# ActiveHeadphonePTH.net
KiCad netlist of a schematic drawn in EAGLE
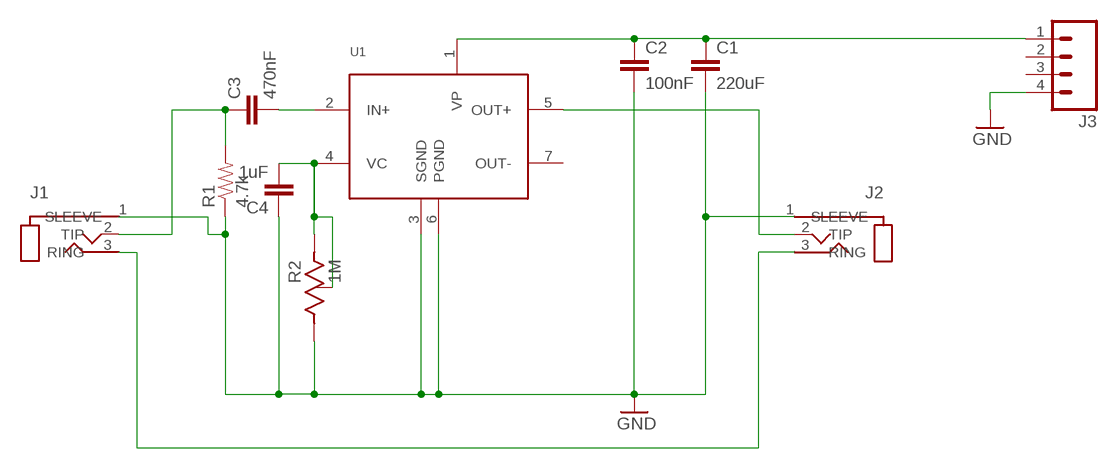
[diagram p0: schematic, sheet 1]

(export (version "E")
  (design (tool "Eeschema 10.0.6"))
  (components
    (comp (ref "C1")
      (value "220uF")
      (footprint "eagle-import:CAP-PTH-5MM")
      (libsource (lib "eagle-import") (part "CAPPTH1"))
    )
    (comp (ref "C2")
      (value "100nF")
      (footprint "eagle-import:CAP-PTH-5MM")
      (libsource (lib "eagle-import") (part "CAPPTH1"))
    )
    (comp (ref "C3")
      (value "470nF")
      (footprint "eagle-import:CAP-PTH-SMALL")
      (libsource (lib "eagle-import") (part "CAPPTH"))
    )
    (comp (ref "C4")
      (value "1uF")
      (footprint "eagle-import:CAP-PTH-SMALL")
      (libsource (lib "eagle-import") (part "CAPPTH"))
    )
    (comp (ref "J1")
      (value "SJ1-35XXPTH")
      (footprint "eagle-import:SJ1-3523N")
      (libsource (lib "eagle-import") (part "SJ1-35XXPTH"))
    )
    (comp (ref "J2")
      (value "SJ1-35XXPTH")
      (footprint "eagle-import:SJ1-3523N")
      (libsource (lib "eagle-import") (part "SJ1-35XXPTH"))
    )
    (comp (ref "J3")
      (value "M04PTH")
      (footprint "eagle-import:1X04")
      (libsource (lib "eagle-import") (part "M04PTH"))
    )
    (comp (ref "R1")
      (value "4.7k")
      (footprint "eagle-import:AXIAL-0.4")
      (libsource (lib "eagle-import") (part "RESISTORPTH-1/4W"))
    )
    (comp (ref "R2")
      (value "1M")
      (footprint "eagle-import:3352T")
      (libsource (lib "eagle-import") (part "3352T"))
    )
    (comp (ref "U1")
      (value "TDA7052")
      (footprint "eagle-import:DIL-8")
      (libsource (lib "eagle-import") (part "TDA7052"))
    )
  )
  (nets
    (net (code "1") (name "GND") (class "Default")
      (node (ref "C1") (pin "2") (pinfunction "2_2") (pintype "passive"))
      (node (ref "C2") (pin "2") (pinfunction "2_2") (pintype "passive"))
      (node (ref "C4") (pin "1") (pinfunction "1_1") (pintype "passive"))
      (node (ref "J1") (pin "1") (pinfunction "SLEEVE_1") (pintype "bidirectional"))
      (node (ref "J2") (pin "1") (pinfunction "SLEEVE_1") (pintype "bidirectional"))
      (node (ref "J3") (pin "4") (pinfunction "4_4") (pintype "passive"))
      (node (ref "R1") (pin "P$1") (pinfunction "1_P$1") (pintype "passive"))
      (node (ref "R2") (pin "1") (pinfunction "CCW_1") (pintype "bidirectional"))
      (node (ref "U1") (pin "3") (pinfunction "SGND_3") (pintype "bidirectional"))
      (node (ref "U1") (pin "6") (pinfunction "PGND_6") (pintype "bidirectional"))
    )
    (net (code "2") (name "Net-(J1-RING)") (class "Default")
      (node (ref "J1") (pin "3") (pinfunction "RING_3") (pintype "bidirectional"))
      (node (ref "J2") (pin "3") (pinfunction "RING_3") (pintype "bidirectional"))
    )
    (net (code "3") (name "Net-(J1-TIP)") (class "Default")
      (node (ref "C3") (pin "1") (pinfunction "1_1") (pintype "passive"))
      (node (ref "J1") (pin "2") (pinfunction "TIP_2") (pintype "bidirectional"))
      (node (ref "R1") (pin "P$2") (pinfunction "2_P$2") (pintype "passive"))
    )
    (net (code "4") (name "Net-(J2-TIP)") (class "Default")
      (node (ref "J2") (pin "2") (pinfunction "TIP_2") (pintype "bidirectional"))
      (node (ref "U1") (pin "5") (pinfunction "OUT+_5") (pintype "bidirectional"))
    )
    (net (code "5") (name "Net-(R2-CW)") (class "Default")
      (node (ref "C4") (pin "2") (pinfunction "2_2") (pintype "passive"))
      (node (ref "R2") (pin "2") (pinfunction "WIPER_2") (pintype "bidirectional"))
      (node (ref "R2") (pin "3") (pinfunction "CW_3") (pintype "bidirectional"))
      (node (ref "U1") (pin "4") (pinfunction "VC_4") (pintype "bidirectional"))
    )
    (net (code "6") (name "Net-(U1-IN+)") (class "Default")
      (node (ref "C3") (pin "2") (pinfunction "2_2") (pintype "passive"))
      (node (ref "U1") (pin "2") (pinfunction "IN+_2") (pintype "bidirectional"))
    )
    (net (code "7") (name "Net-(U1-VP)") (class "Default")
      (node (ref "C1") (pin "1") (pinfunction "1_1") (pintype "passive"))
      (node (ref "C2") (pin "1") (pinfunction "1_1") (pintype "passive"))
      (node (ref "J3") (pin "1") (pinfunction "1_1") (pintype "passive"))
      (node (ref "U1") (pin "1") (pinfunction "VP_1") (pintype "bidirectional"))
    )
    (net (code "8") (name "unconnected-(J3-Pad2)") (class "Default")
      (node (ref "J3") (pin "2") (pinfunction "2_2") (pintype "passive"))
    )
    (net (code "9") (name "unconnected-(J3-Pad3)") (class "Default")
      (node (ref "J3") (pin "3") (pinfunction "3_3") (pintype "passive"))
    )
    (net (code "10") (name "unconnected-(U1-OUT--Pad7)") (class "Default")
      (node (ref "U1") (pin "7") (pinfunction "OUT-_7") (pintype "bidirectional"))
    )
  )
)
